# OK1050-C_V1_2_Connect.net
KiCad netlist of a schematic drawn in Altium Designer
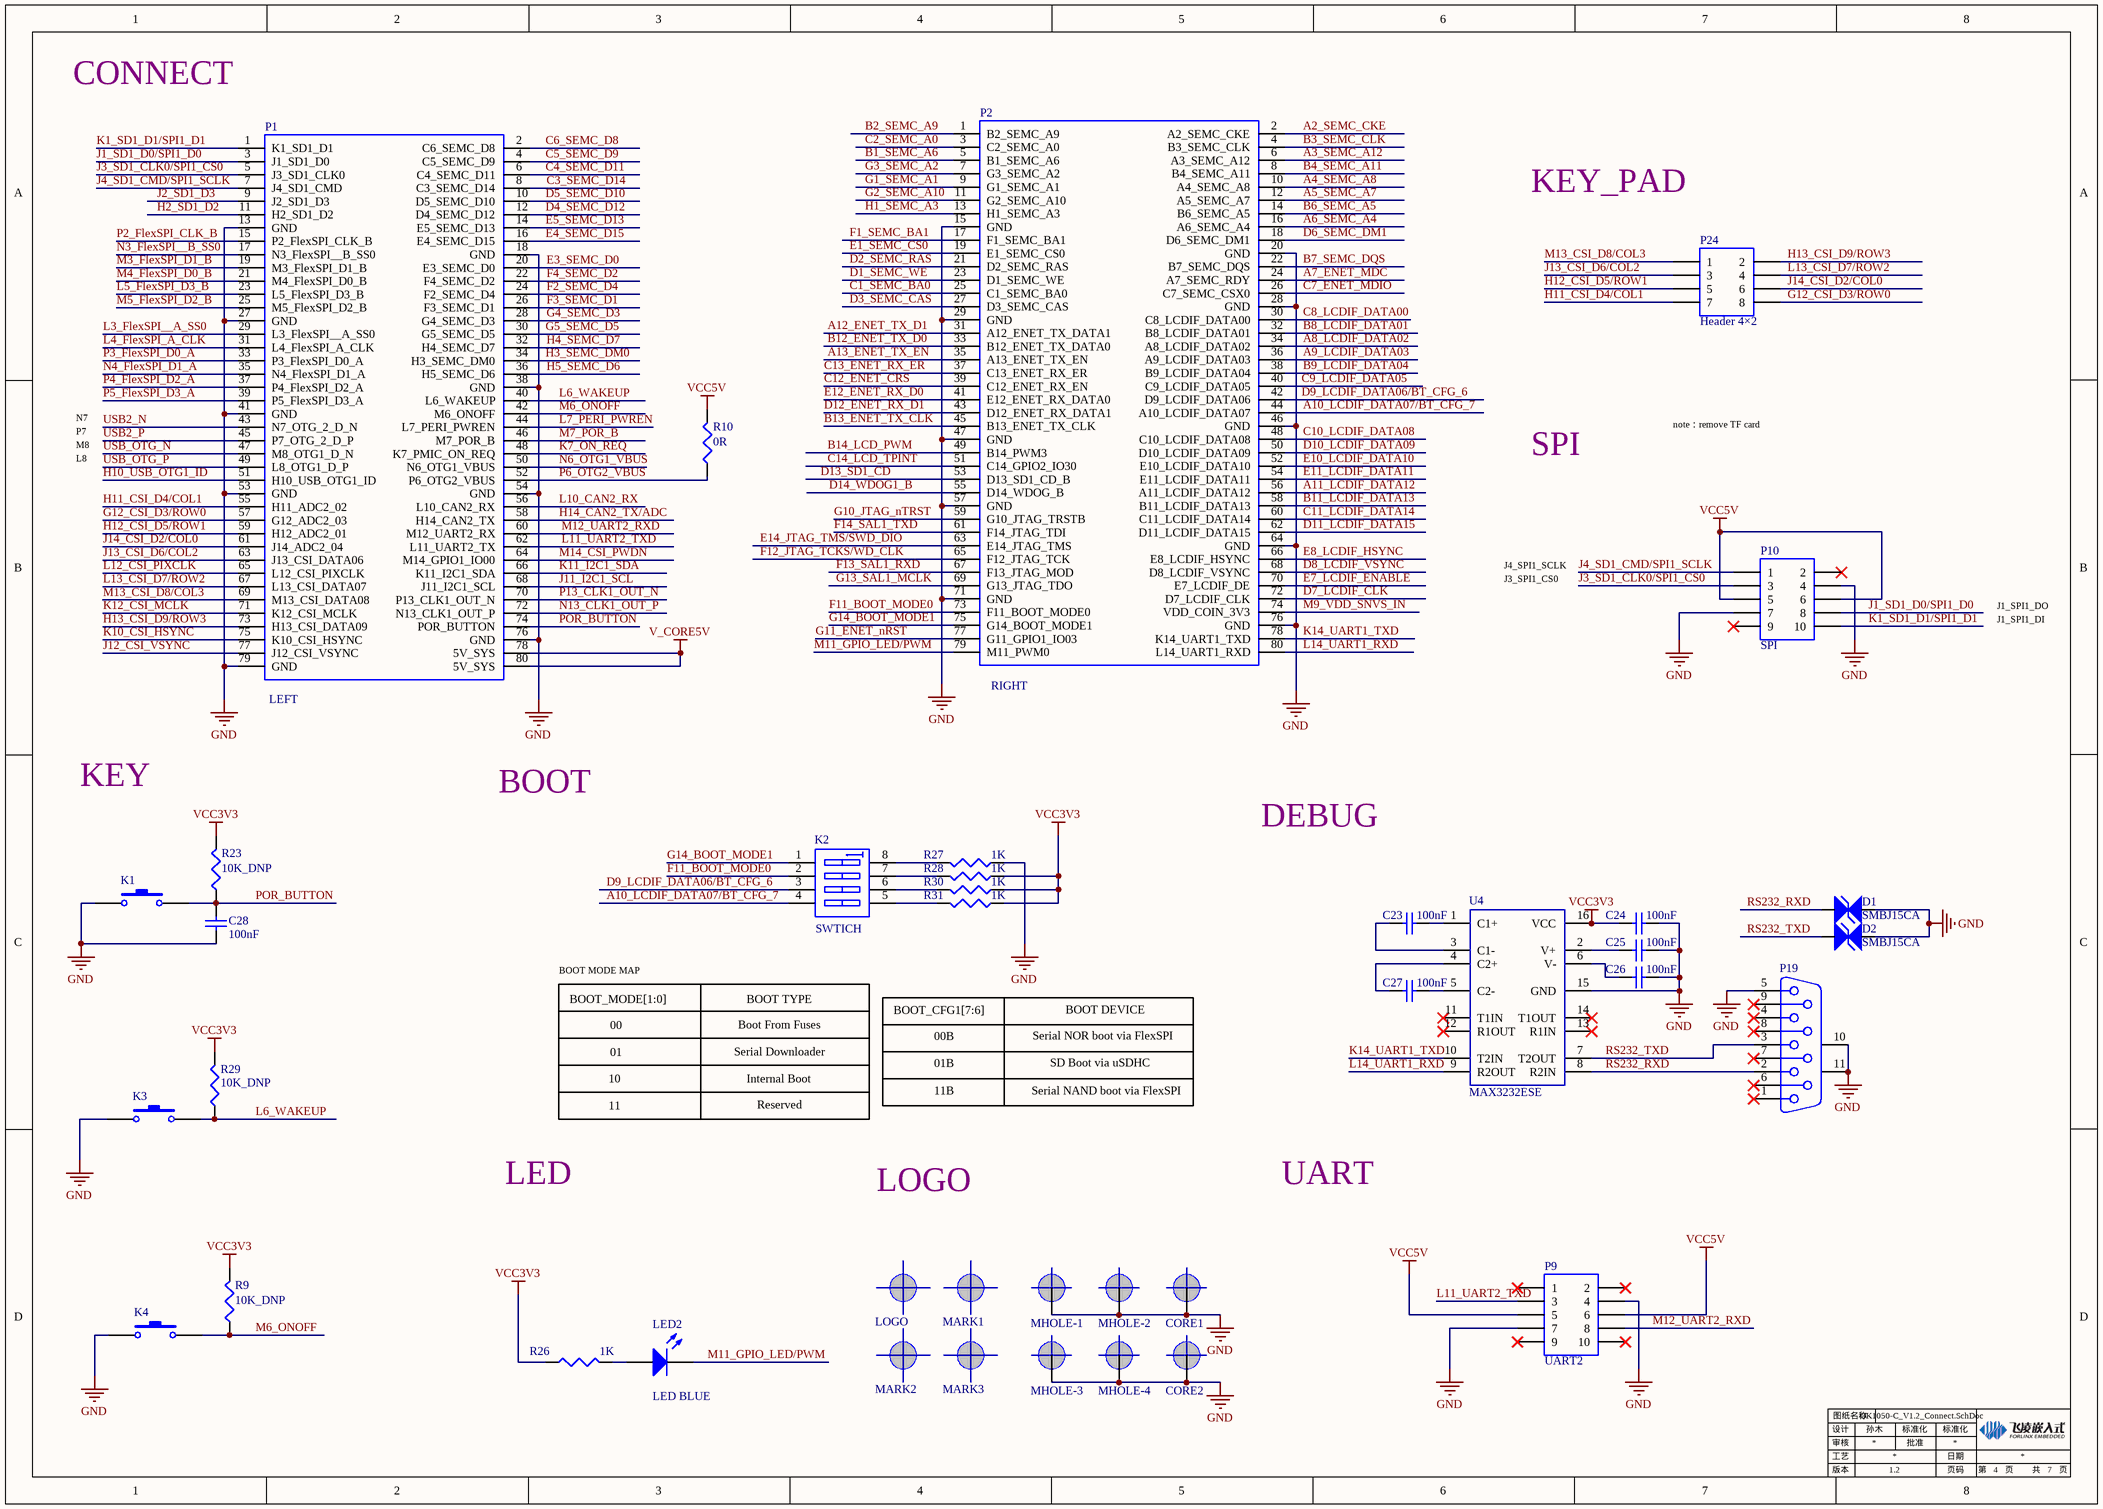
[diagram p0: OK1050-C_V1.2_Connect.SchDoc]

(export (version "E")
  (design (tool "Eeschema 10.0.6"))
  (components
    (comp (ref "C23")
      (value "100nF")
      (footprint "0603C+")
      (description "Capacitor")
      (fields (field (name "PUBLISHER") "Altium Limited"))
      (libsource (lib "Miscellaneous Devices") (part "Cap"))
    )
    (comp (ref "C24")
      (value "100nF")
      (footprint "0603C+")
      (description "Capacitor")
      (fields (field (name "PUBLISHER") "Altium Limited"))
      (libsource (lib "Miscellaneous Devices") (part "Cap"))
    )
    (comp (ref "C25")
      (value "100nF")
      (footprint "0603C+")
      (description "Capacitor")
      (fields (field (name "PUBLISHER") "Altium Limited"))
      (libsource (lib "Miscellaneous Devices") (part "Cap"))
    )
    (comp (ref "C26")
      (value "100nF")
      (footprint "0603C+")
      (description "Capacitor")
      (fields (field (name "PUBLISHER") "Altium Limited"))
      (libsource (lib "Miscellaneous Devices") (part "Cap"))
    )
    (comp (ref "C27")
      (value "100nF")
      (footprint "0603C+")
      (description "Capacitor")
      (fields (field (name "PUBLISHER") "Altium Limited"))
      (libsource (lib "Miscellaneous Devices") (part "Cap"))
    )
    (comp (ref "C28")
      (value "100nF")
      (footprint "0603C+")
      (description "Capacitor")
      (fields (field (name "PUBLISHER") "Altium Limited"))
      (libsource (lib "Miscellaneous Devices") (part "Cap"))
    )
    (comp (ref "D1") (value "SMBJ15CA") (footprint "SMB/DO-214AA") (libsource (lib "Sch") (part "TVS")))
    (comp (ref "D2") (value "SMBJ15CA") (footprint "SMB/DO-214AA") (libsource (lib "Sch") (part "TVS")))
    (comp (ref "K1")
      (value "6*6*5侧位带支架")
      (description "Switch")
      (fields (field (name "PUBLISHER") "Altium Limited"))
      (libsource (lib "Miscellaneous Devices") (part "SW-PB"))
    )
    (comp (ref "K2")
      (value "SWTICH")
      (footprint "SMD_4")
      (libsource (lib "PCB_RT1052_1") (part "SWTICH_DIP6"))
    )
    (comp (ref "K3")
      (value "6*6*5侧位2脚带支架")
      (description "Switch")
      (fields (field (name "PUBLISHER") "Altium Limited"))
      (libsource (lib "Miscellaneous Devices") (part "SW-PB"))
    )
    (comp (ref "K4")
      (value "6*6*5侧位2脚带支架")
      (description "Switch")
      (fields (field (name "PUBLISHER") "Altium Limited"))
      (libsource (lib "Miscellaneous Devices") (part "SW-PB"))
    )
    (comp (ref "LED2")
      (value "LED_BULE")
      (footprint "LED0603_M1608")
      (description "Typical RED, GREEN, YELLOW, AMBER GaAs LED")
      (fields (field (name "BOOK") "LED BLUE") (field (name "PUBLISHER") "Altium Limited"))
      (libsource (lib "NET-LCD-USB") (part "LED2"))
    )
    (comp (ref "LOGO1") (value "LOGO") (footprint "LOGO") (libsource (lib "IMX6QP-C") (part "MHOLE_1")))
    (comp (ref "M1")
      (value "MHOLE-1")
      (footprint "3.2mm_hole")
      (libsource (lib "IMX6QP-C") (part "MHOLE-2_1"))
    )
    (comp (ref "M2") (value "MHOLE-2") (footprint "3.2mm_hole") (libsource (lib "IMX6QP-C") (part "MHOLE-2")))
    (comp (ref "M3")
      (value "MHOLE-3")
      (footprint "3.2mm_hole")
      (libsource (lib "IMX6QP-C") (part "MHOLE-2_1"))
    )
    (comp (ref "M4")
      (value "MHOLE-4")
      (footprint "3.2mm_hole")
      (libsource (lib "IMX6QP-C") (part "MHOLE-2_1"))
    )
    (comp (ref "M5") (value "CORE1") (footprint "2.1mm_hole") (libsource (lib "IMX6QP-C") (part "MHOLE-2")))
    (comp (ref "M6") (value "CORE2") (footprint "2.1mm_hole") (libsource (lib "IMX6QP-C") (part "MHOLE-2_1")))
    (comp (ref "Mark1") (value "MARK1") (footprint "MARK POINT") (libsource (lib "IMX6QP-C") (part "MHOLE")))
    (comp (ref "Mark2") (value "MARK2") (footprint "MARK POINT") (libsource (lib "IMX6QP-C") (part "MHOLE")))
    (comp (ref "Mark3") (value "MARK3") (footprint "MARK POINT") (libsource (lib "IMX6QP-C") (part "MHOLE")))
    (comp (ref "P1")
      (value "LEFT")
      (footprint "CON80")
      (description "Header, 30-Pin, Dual row")
      (fields (field (name "PUBLISHER") "Altium Limited"))
      (libsource (lib "PCB_RT1052_1") (part "Header40X2_left"))
    )
    (comp (ref "P2")
      (value "RIGHT")
      (footprint "CON80")
      (description "Header, 30-Pin, Dual row")
      (fields (field (name "PUBLISHER") "Altium Limited"))
      (libsource (lib "PCB_RT1052_1") (part "Header40X2_right"))
    )
    (comp (ref "P9")
      (value "UART2")
      (description "Header, 5-Pin, Dual row")
      (fields (field (name "PUBLISHER") "Altium Limited"))
      (libsource (lib "PCB_RT1052") (part "Header 5X2"))
    )
    (comp (ref "P10")
      (value "SPI")
      (description "Header, 5-Pin, Dual row")
      (fields (field (name "PUBLISHER") "Altium Limited"))
      (libsource (lib "PCB_RT1052") (part "Header 5X2"))
    )
    (comp (ref "P19")
      (value "DEBUG")
      (footprint "DSUB1.385-2H9-M")
      (description "Receptacle Assembly, 9 Position, Right Angle")
      (fields (field (name "PUBLISHER") "Altium Limited"))
      (libsource (lib "Miscellaneous Connectors") (part "D Connector 9"))
    )
    (comp (ref "P24")
      (value "Header 4×2")
      (footprint "HDR2X4")
      (libsource (lib "PCB_RT1052") (part "Header 4×2"))
    )
    (comp (ref "R9")
      (value "10K_DNP")
      (footprint "0603R+")
      (description "Resistor")
      (fields (field (name "PUBLISHER") "Altium Limited"))
      (libsource (lib "Miscellaneous Devices") (part "Res3"))
    )
    (comp (ref "R10")
      (value "0R")
      (footprint "0603R+")
      (description "Resistor")
      (fields (field (name "PUBLISHER") "Altium Limited"))
      (libsource (lib "Miscellaneous Devices") (part "Res3"))
    )
    (comp (ref "R23")
      (value "10K_DNP")
      (footprint "0603R+")
      (description "Resistor")
      (fields (field (name "PUBLISHER") "Altium Limited"))
      (libsource (lib "Miscellaneous Devices") (part "Res3"))
    )
    (comp (ref "R26")
      (value "1K")
      (footprint "0603R+")
      (description "Resistor")
      (fields (field (name "PUBLISHER") "Altium Limited"))
      (libsource (lib "Miscellaneous Devices") (part "Res3"))
    )
    (comp (ref "R27")
      (value "1K")
      (footprint "0603R+")
      (description "Resistor")
      (fields (field (name "PUBLISHER") "Altium Limited"))
      (libsource (lib "Miscellaneous Devices") (part "Res3"))
    )
    (comp (ref "R28")
      (value "1K")
      (footprint "0603R+")
      (description "Resistor")
      (fields (field (name "PUBLISHER") "Altium Limited"))
      (libsource (lib "Miscellaneous Devices") (part "Res3"))
    )
    (comp (ref "R29")
      (value "10K_DNP")
      (footprint "0603R+")
      (description "Resistor")
      (fields (field (name "PUBLISHER") "Altium Limited"))
      (libsource (lib "Miscellaneous Devices") (part "Res3"))
    )
    (comp (ref "R30")
      (value "1K")
      (footprint "0603R+")
      (description "Resistor")
      (fields (field (name "PUBLISHER") "Altium Limited"))
      (libsource (lib "Miscellaneous Devices") (part "Res3"))
    )
    (comp (ref "R31")
      (value "1K")
      (footprint "0603R+")
      (description "Resistor")
      (fields (field (name "PUBLISHER") "Altium Limited"))
      (libsource (lib "Miscellaneous Devices") (part "Res3"))
    )
    (comp (ref "U4") (value "MAX3232ESE") (footprint "SOIC-16N") (libsource (lib "Sch") (part "MAX3232")))
  )
  (nets
    (net (code "1") (name "/A2_SEMC_CKE") (class "Default")
      (node (ref "P2") (pin "2") (pinfunction "A2_SEMC_CKE_2") (pintype "passive"))
    )
    (net (code "2") (name "/A3_SEMC_A12") (class "Default")
      (node (ref "P2") (pin "6") (pinfunction "A3_SEMC_A12_6") (pintype "passive"))
    )
    (net (code "3") (name "/A4_SEMC_A8") (class "Default")
      (node (ref "P2") (pin "10") (pinfunction "A4_SEMC_A8_10") (pintype "passive"))
    )
    (net (code "4") (name "/A5_SEMC_A7") (class "Default")
      (node (ref "P2") (pin "12") (pinfunction "A5_SEMC_A7_12") (pintype "passive"))
    )
    (net (code "5") (name "/A6_SEMC_A4") (class "Default")
      (node (ref "P2") (pin "16") (pinfunction "A6_SEMC_A4_16") (pintype "passive"))
    )
    (net (code "6") (name "/A7_ENET_MDC") (class "Default")
      (node (ref "P2") (pin "24") (pinfunction "A7_SEMC_RDY_24") (pintype "passive"))
    )
    (net (code "7") (name "/A8_LCDIF_DATA02") (class "Default")
      (node (ref "P2") (pin "34") (pinfunction "A8_LCDIF_DATA02_34") (pintype "passive"))
    )
    (net (code "8") (name "/A9_LCDIF_DATA03") (class "Default")
      (node (ref "P2") (pin "36") (pinfunction "A9_LCDIF_DATA03_36") (pintype "passive"))
    )
    (net (code "9") (name "/A10_LCDIF_DATA07{slash}BT_CFG_7") (class "Default")
      (node (ref "K2") (pin "4") (pinfunction "A4_4") (pintype "passive"))
      (node (ref "P2") (pin "44") (pinfunction "A10_LCDIF_DATA07_44") (pintype "passive"))
    )
    (net (code "10") (name "/A11_LCDIF_DATA12") (class "Default")
      (node (ref "P2") (pin "56") (pinfunction "A11_LCDIF_DATA12_56") (pintype "passive"))
    )
    (net (code "11") (name "/A12_ENET_TX_D1") (class "Default")
      (node (ref "P2") (pin "31") (pinfunction "A12_ENET_TX_DATA1_31") (pintype "passive"))
    )
    (net (code "12") (name "/A13_ENET_TX_EN") (class "Default")
      (node (ref "P2") (pin "35") (pinfunction "A13_ENET_TX_EN_35") (pintype "passive"))
    )
    (net (code "13") (name "/B1_SEMC_A6") (class "Default")
      (node (ref "P2") (pin "5") (pinfunction "B1_SEMC_A6_5") (pintype "passive"))
    )
    (net (code "14") (name "/B2_SEMC_A9") (class "Default")
      (node (ref "P2") (pin "1") (pinfunction "B2_SEMC_A9_1") (pintype "passive"))
    )
    (net (code "15") (name "/B3_SEMC_CLK") (class "Default")
      (node (ref "P2") (pin "4") (pinfunction "B3_SEMC_CLK_4") (pintype "passive"))
    )
    (net (code "16") (name "/B4_SEMC_A11") (class "Default")
      (node (ref "P2") (pin "8") (pinfunction "B4_SEMC_A11_8") (pintype "passive"))
    )
    (net (code "17") (name "/B6_SEMC_A5") (class "Default")
      (node (ref "P2") (pin "14") (pinfunction "B6_SEMC_A5_14") (pintype "passive"))
    )
    (net (code "18") (name "/B7_SEMC_DQS") (class "Default")
      (node (ref "P2") (pin "22") (pinfunction "B7_SEMC_DQS_22") (pintype "passive"))
    )
    (net (code "19") (name "/B8_LCDIF_DATA01") (class "Default")
      (node (ref "P2") (pin "32") (pinfunction "B8_LCDIF_DATA01_32") (pintype "passive"))
    )
    (net (code "20") (name "/B9_LCDIF_DATA04") (class "Default")
      (node (ref "P2") (pin "38") (pinfunction "B9_LCDIF_DATA04_38") (pintype "passive"))
    )
    (net (code "21") (name "/B11_LCDIF_DATA13") (class "Default")
      (node (ref "P2") (pin "58") (pinfunction "B11_LCDIF_DATA13_58") (pintype "passive"))
    )
    (net (code "22") (name "/B12_ENET_TX_D0") (class "Default")
      (node (ref "P2") (pin "33") (pinfunction "B12_ENET_TX_DATA0_33") (pintype "passive"))
    )
    (net (code "23") (name "/B13_ENET_TX_CLK") (class "Default")
      (node (ref "P2") (pin "45") (pinfunction "B13_ENET_TX_CLK_45") (pintype "passive"))
    )
    (net (code "24") (name "/B14_LCD_PWM") (class "Default")
      (node (ref "P2") (pin "49") (pinfunction "B14_PWM3_49") (pintype "passive"))
    )
    (net (code "25") (name "/C1_SEMC_BA0") (class "Default")
      (node (ref "P2") (pin "25") (pinfunction "C1_SEMC_BA0_25") (pintype "passive"))
    )
    (net (code "26") (name "/C2_SEMC_A0") (class "Default")
      (node (ref "P2") (pin "3") (pinfunction "C2_SEMC_A0_3") (pintype "passive"))
    )
    (net (code "27") (name "/C3_SEMC_D14") (class "Default")
      (node (ref "P1") (pin "8") (pinfunction "C3_SEMC_D14_8") (pintype "passive"))
    )
    (net (code "28") (name "/C4_SEMC_D11") (class "Default")
      (node (ref "P1") (pin "6") (pinfunction "C4_SEMC_D11_6") (pintype "passive"))
    )
    (net (code "29") (name "/C5_SEMC_D9") (class "Default")
      (node (ref "P1") (pin "4") (pinfunction "C5_SEMC_D9_4") (pintype "passive"))
    )
    (net (code "30") (name "/C6_SEMC_D8") (class "Default")
      (node (ref "P1") (pin "2") (pinfunction "C6_SEMC_D8_2") (pintype "passive"))
    )
    (net (code "31") (name "/C7_ENET_MDIO") (class "Default")
      (node (ref "P2") (pin "26") (pinfunction "C7_SEMC_CSX0_26") (pintype "passive"))
    )
    (net (code "32") (name "/C8_LCDIF_DATA00") (class "Default")
      (node (ref "P2") (pin "30") (pinfunction "C8_LCDIF_DATA00_30") (pintype "passive"))
    )
    (net (code "33") (name "/C9_LCDIF_DATA05") (class "Default")
      (node (ref "P2") (pin "40") (pinfunction "C9_LCDIF_DATA05_40") (pintype "passive"))
    )
    (net (code "34") (name "/C10_LCDIF_DATA08") (class "Default")
      (node (ref "P2") (pin "48") (pinfunction "C10_LCDIF_DATA08_48") (pintype "passive"))
    )
    (net (code "35") (name "/C11_LCDIF_DATA14") (class "Default")
      (node (ref "P2") (pin "60") (pinfunction "C11_LCDIF_DATA14_60") (pintype "passive"))
    )
    (net (code "36") (name "/C12_ENET_CRS") (class "Default")
      (node (ref "P2") (pin "39") (pinfunction "C12_ENET_RX_EN_39") (pintype "passive"))
    )
    (net (code "37") (name "/C13_ENET_RX_ER") (class "Default")
      (node (ref "P2") (pin "37") (pinfunction "C13_ENET_RX_ER_37") (pintype "passive"))
    )
    (net (code "38") (name "/C14_LCD_TPINT") (class "Default")
      (node (ref "P2") (pin "51") (pinfunction "C14_GPIO2_IO30_51") (pintype "passive"))
    )
    (net (code "39") (name "/D1_SEMC_WE") (class "Default")
      (node (ref "P2") (pin "23") (pinfunction "D1_SEMC_WE_23") (pintype "passive"))
    )
    (net (code "40") (name "/D2_SEMC_RAS") (class "Default")
      (node (ref "P2") (pin "21") (pinfunction "D2_SEMC_RAS_21") (pintype "passive"))
    )
    (net (code "41") (name "/D3_SEMC_CAS") (class "Default")
      (node (ref "P2") (pin "27") (pinfunction "D3_SEMC_CAS_27") (pintype "passive"))
    )
    (net (code "42") (name "/D4_SEMC_D12") (class "Default")
      (node (ref "P1") (pin "12") (pinfunction "D4_SEMC_D12_12") (pintype "passive"))
    )
    (net (code "43") (name "/D5_SEMC_D10") (class "Default")
      (node (ref "P1") (pin "10") (pinfunction "D5_SEMC_D10_10") (pintype "passive"))
    )
    (net (code "44") (name "/D6_SEMC_DM1") (class "Default")
      (node (ref "P2") (pin "18") (pinfunction "D6_SEMC_DM1_18") (pintype "passive"))
    )
    (net (code "45") (name "/D7_LCDIF_CLK") (class "Default")
      (node (ref "P2") (pin "72") (pinfunction "D7_LCDIF_CLK_72") (pintype "passive"))
    )
    (net (code "46") (name "/D8_LCDIF_VSYNC") (class "Default")
      (node (ref "P2") (pin "68") (pinfunction "D8_LCDIF_VSYNC_68") (pintype "passive"))
    )
    (net (code "47") (name "/D9_LCDIF_DATA06{slash}BT_CFG_6") (class "Default")
      (node (ref "K2") (pin "3") (pinfunction "A3_3") (pintype "passive"))
      (node (ref "P2") (pin "42") (pinfunction "D9_LCDIF_DATA06_42") (pintype "passive"))
    )
    (net (code "48") (name "/D10_LCDIF_DATA09") (class "Default")
      (node (ref "P2") (pin "50") (pinfunction "D10_LCDIF_DATA09_50") (pintype "passive"))
    )
    (net (code "49") (name "/D11_LCDIF_DATA15") (class "Default")
      (node (ref "P2") (pin "62") (pinfunction "D11_LCDIF_DATA15_62") (pintype "passive"))
    )
    (net (code "50") (name "/D12_ENET_RX_D1") (class "Default")
      (node (ref "P2") (pin "43") (pinfunction "D12_ENET_RX_DATA1_43") (pintype "passive"))
    )
    (net (code "51") (name "/D13_SD1_CD") (class "Default")
      (node (ref "P2") (pin "53") (pinfunction "D13_SD1_CD_B_53") (pintype "passive"))
    )
    (net (code "52") (name "/D14_WDOG1_B") (class "Default")
      (node (ref "P2") (pin "55") (pinfunction "D14_WDOG_B_55") (pintype "passive"))
    )
    (net (code "53") (name "/E1_SEMC_CS0") (class "Default")
      (node (ref "P2") (pin "19") (pinfunction "E1_SEMC_CS0_19") (pintype "passive"))
    )
    (net (code "54") (name "/E3_SEMC_D0") (class "Default")
      (node (ref "P1") (pin "20") (pinfunction "E3_SEMC_D0_20") (pintype "passive"))
    )
    (net (code "55") (name "/E4_SEMC_D15") (class "Default")
      (node (ref "P1") (pin "16") (pinfunction "E4_SEMC_D15_16") (pintype "passive"))
    )
    (net (code "56") (name "/E5_SEMC_D13") (class "Default")
      (node (ref "P1") (pin "14") (pinfunction "E5_SEMC_D13_14") (pintype "passive"))
    )
    (net (code "57") (name "/E7_LCDIF_ENABLE") (class "Default")
      (node (ref "P2") (pin "70") (pinfunction "E7_LCDIF_DE_70") (pintype "passive"))
    )
    (net (code "58") (name "/E8_LCDIF_HSYNC") (class "Default")
      (node (ref "P2") (pin "66") (pinfunction "E8_LCDIF_HSYNC_66") (pintype "passive"))
    )
    (net (code "59") (name "/E10_LCDIF_DATA10") (class "Default")
      (node (ref "P2") (pin "52") (pinfunction "E10_LCDIF_DATA10_52") (pintype "passive"))
    )
    (net (code "60") (name "/E11_LCDIF_DATA11") (class "Default")
      (node (ref "P2") (pin "54") (pinfunction "E11_LCDIF_DATA11_54") (pintype "passive"))
    )
    (net (code "61") (name "/E12_ENET_RX_D0") (class "Default")
      (node (ref "P2") (pin "41") (pinfunction "E12_ENET_RX_DATA0_41") (pintype "passive"))
    )
    (net (code "62") (name "/E14_JTAG_TMS{slash}SWD_DIO") (class "Default")
      (node (ref "P2") (pin "63") (pinfunction "E14_JTAG_TMS_63") (pintype "passive"))
    )
    (net (code "63") (name "/F1_SEMC_BA1") (class "Default")
      (node (ref "P2") (pin "17") (pinfunction "F1_SEMC_BA1_17") (pintype "passive"))
    )
    (net (code "64") (name "/F2_SEMC_D4") (class "Default")
      (node (ref "P1") (pin "24") (pinfunction "F2_SEMC_D4_24") (pintype "passive"))
    )
    (net (code "65") (name "/F3_SEMC_D1") (class "Default")
      (node (ref "P1") (pin "26") (pinfunction "F3_SEMC_D1_26") (pintype "passive"))
    )
    (net (code "66") (name "/F4_SEMC_D2") (class "Default")
      (node (ref "P1") (pin "22") (pinfunction "F4_SEMC_D2_22") (pintype "passive"))
    )
    (net (code "67") (name "/F11_BOOT_MODE0") (class "Default")
      (node (ref "K2") (pin "2") (pinfunction "A2_2") (pintype "passive"))
      (node (ref "P2") (pin "73") (pinfunction "F11_BOOT_MODE0_73") (pintype "passive"))
    )
    (net (code "68") (name "/F12_JTAG_TCKS{slash}WD_CLK") (class "Default")
      (node (ref "P2") (pin "65") (pinfunction "F12_JTAG_TCK_65") (pintype "passive"))
    )
    (net (code "69") (name "/F13_SAL1_RXD") (class "Default")
      (node (ref "P2") (pin "67") (pinfunction "F13_JTAG_MOD_67") (pintype "passive"))
    )
    (net (code "70") (name "/F14_SAL1_TXD") (class "Default")
      (node (ref "P2") (pin "61") (pinfunction "F14_JTAG_TDI_61") (pintype "passive"))
    )
    (net (code "71") (name "/G1_SEMC_A1") (class "Default")
      (node (ref "P2") (pin "9") (pinfunction "G1_SEMC_A1_9") (pintype "passive"))
    )
    (net (code "72") (name "/G2_SEMC_A10") (class "Default")
      (node (ref "P2") (pin "11") (pinfunction "G2_SEMC_A10_11") (pintype "passive"))
    )
    (net (code "73") (name "/G3_SEMC_A2") (class "Default")
      (node (ref "P2") (pin "7") (pinfunction "G3_SEMC_A2_7") (pintype "passive"))
    )
    (net (code "74") (name "/G4_SEMC_D3") (class "Default")
      (node (ref "P1") (pin "28") (pinfunction "G4_SEMC_D3_28") (pintype "passive"))
    )
    (net (code "75") (name "/G5_SEMC_D5") (class "Default")
      (node (ref "P1") (pin "30") (pinfunction "G5_SEMC_D5_30") (pintype "passive"))
    )
    (net (code "76") (name "/G10_JTAG_nTRST") (class "Default")
      (node (ref "P2") (pin "59") (pinfunction "G10_JTAG_TRSTB_59") (pintype "passive"))
    )
    (net (code "77") (name "/G11_ENET_nRST") (class "Default")
      (node (ref "P2") (pin "77") (pinfunction "G11_GPIO1_IO03_77") (pintype "passive"))
    )
    (net (code "78") (name "/G12_CSI_D3{slash}ROW0") (class "Default")
      (node (ref "P1") (pin "57") (pinfunction "G12_ADC2_03_57") (pintype "passive"))
      (node (ref "P24") (pin "8") (pinfunction "8_8") (pintype "passive"))
    )
    (net (code "79") (name "/G13_SAL1_MCLK") (class "Default")
      (node (ref "P2") (pin "69") (pinfunction "G13_JTAG_TDO_69") (pintype "passive"))
    )
    (net (code "80") (name "/G14_BOOT_MODE1") (class "Default")
      (node (ref "K2") (pin "1") (pinfunction "A1_1") (pintype "passive"))
      (node (ref "P2") (pin "75") (pinfunction "G14_BOOT_MODE1_75") (pintype "passive"))
    )
    (net (code "81") (name "/H1_SEMC_A3") (class "Default")
      (node (ref "P2") (pin "13") (pinfunction "H1_SEMC_A3_13") (pintype "passive"))
    )
    (net (code "82") (name "/H2_SD1_D2") (class "Default")
      (node (ref "P1") (pin "11") (pinfunction "H2_SD1_D2_11") (pintype "passive"))
    )
    (net (code "83") (name "/H3_SEMC_DM0") (class "Default")
      (node (ref "P1") (pin "34") (pinfunction "H3_SEMC_DM0_34") (pintype "passive"))
    )
    (net (code "84") (name "/H4_SEMC_D7") (class "Default")
      (node (ref "P1") (pin "32") (pinfunction "H4_SEMC_D7_32") (pintype "passive"))
    )
    (net (code "85") (name "/H5_SEMC_D6") (class "Default")
      (node (ref "P1") (pin "36") (pinfunction "H5_SEMC_D6_36") (pintype "passive"))
    )
    (net (code "86") (name "/H10_USB_OTG1_ID") (class "Default")
      (node (ref "P1") (pin "51") (pinfunction "H10_USB_OTG1_ID_51") (pintype "passive"))
    )
    (net (code "87") (name "/H11_CSI_D4{slash}COL1") (class "Default")
      (node (ref "P1") (pin "55") (pinfunction "H11_ADC2_02_55") (pintype "passive"))
      (node (ref "P24") (pin "7") (pinfunction "7_7") (pintype "passive"))
    )
    (net (code "88") (name "/H12_CSI_D5{slash}ROW1") (class "Default")
      (node (ref "P1") (pin "59") (pinfunction "H12_ADC2_01_59") (pintype "passive"))
      (node (ref "P24") (pin "5") (pinfunction "5_5") (pintype "passive"))
    )
    (net (code "89") (name "/H13_CSI_D9{slash}ROW3") (class "Default")
      (node (ref "P1") (pin "73") (pinfunction "H13_CSI_DATA09_73") (pintype "passive"))
      (node (ref "P24") (pin "2") (pinfunction "2_2") (pintype "passive"))
    )
    (net (code "90") (name "/H14_CAN2_TX{slash}ADC") (class "Default")
      (node (ref "P1") (pin "58") (pinfunction "H14_CAN2_TX_58") (pintype "passive"))
    )
    (net (code "91") (name "/J1_SD1_D0{slash}SPI1_D0") (class "Default")
      (node (ref "P1") (pin "3") (pinfunction "J1_SD1_D0_3") (pintype "passive"))
      (node (ref "P10") (pin "8") (pinfunction "8_8") (pintype "passive"))
    )
    (net (code "92") (name "/J2_SD1_D3") (class "Default")
      (node (ref "P1") (pin "9") (pinfunction "J2_SD1_D3_9") (pintype "passive"))
    )
    (net (code "93") (name "/J3_SD1_CLK0{slash}SPI1_CS0") (class "Default")
      (node (ref "P1") (pin "5") (pinfunction "J3_SD1_CLK0_5") (pintype "passive"))
      (node (ref "P10") (pin "3") (pinfunction "3_3") (pintype "passive"))
    )
    (net (code "94") (name "/J4_SD1_CMD{slash}SPI1_SCLK") (class "Default")
      (node (ref "P1") (pin "7") (pinfunction "J4_SD1_CMD_7") (pintype "passive"))
      (node (ref "P10") (pin "1") (pinfunction "1_1") (pintype "passive"))
    )
    (net (code "95") (name "/J11_I2C1_SCL") (class "Default")
      (node (ref "P1") (pin "68") (pinfunction "J11_I2C1_SCL_68") (pintype "passive"))
    )
    (net (code "96") (name "/J12_CSI_VSYNC") (class "Default")
      (node (ref "P1") (pin "77") (pinfunction "J12_CSI_VSYNC_77") (pintype "passive"))
    )
    (net (code "97") (name "/J13_CSI_D6{slash}COL2") (class "Default")
      (node (ref "P1") (pin "63") (pinfunction "J13_CSI_DATA06_63") (pintype "passive"))
      (node (ref "P24") (pin "3") (pinfunction "3_3") (pintype "passive"))
    )
    (net (code "98") (name "/J14_CSI_D2{slash}COL0") (class "Default")
      (node (ref "P1") (pin "61") (pinfunction "J14_ADC2_04_61") (pintype "passive"))
      (node (ref "P24") (pin "6") (pinfunction "6_6") (pintype "passive"))
    )
    (net (code "99") (name "/K1_SD1_D1{slash}SPI1_D1") (class "Default")
      (node (ref "P1") (pin "1") (pinfunction "K1_SD1_D1_1") (pintype "passive"))
      (node (ref "P10") (pin "10") (pinfunction "10_10") (pintype "passive"))
    )
    (net (code "100") (name "/K7_ON_REQ") (class "Default")
      (node (ref "P1") (pin "48") (pinfunction "K7_PMIC_ON_REQ_48") (pintype "passive"))
    )
    (net (code "101") (name "/K10_CSI_HSYNC") (class "Default")
      (node (ref "P1") (pin "75") (pinfunction "K10_CSI_HSYNC_75") (pintype "passive"))
    )
    (net (code "102") (name "/K11_I2C1_SDA") (class "Default")
      (node (ref "P1") (pin "66") (pinfunction "K11_I2C1_SDA_66") (pintype "passive"))
    )
    (net (code "103") (name "/K12_CSI_MCLK") (class "Default")
      (node (ref "P1") (pin "71") (pinfunction "K12_CSI_MCLK_71") (pintype "passive"))
    )
    (net (code "104") (name "/K14_UART1_TXD") (class "Default")
      (node (ref "P2") (pin "78") (pinfunction "K14_UART1_TXD_78") (pintype "passive"))
      (node (ref "U4") (pin "10") (pinfunction "T2IN_10") (pintype "passive"))
    )
    (net (code "105") (name "/L3_FlexSPI__A_SS0") (class "Default")
      (node (ref "P1") (pin "29") (pinfunction "L3_FlexSPI__A_SS0_29") (pintype "passive"))
    )
    (net (code "106") (name "/L4_FlexSPI_A_CLK") (class "Default")
      (node (ref "P1") (pin "31") (pinfunction "L4_FlexSPI_A_CLK_31") (pintype "passive"))
    )
    (net (code "107") (name "/L5_FlexSPI_D3_B") (class "Default")
      (node (ref "P1") (pin "23") (pinfunction "L5_FlexSPI_D3_B_23") (pintype "passive"))
    )
    (net (code "108") (name "/L6_WAKEUP") (class "Default")
      (node (ref "K3") (pin "2") (pinfunction "2_2") (pintype "passive"))
      (node (ref "P1") (pin "40") (pinfunction "L6_WAKEUP_40") (pintype "passive"))
      (node (ref "R29") (pin "1") (pinfunction "1_1") (pintype "passive"))
    )
    (net (code "109") (name "/L7_PERI_PWREN") (class "Default")
      (node (ref "P1") (pin "44") (pinfunction "L7_PERI_PWREN_44") (pintype "passive"))
    )
    (net (code "110") (name "/L10_CAN2_RX") (class "Default")
      (node (ref "P1") (pin "56") (pinfunction "L10_CAN2_RX_56") (pintype "passive"))
    )
    (net (code "111") (name "/L11_UART2_TXD") (class "Default")
      (node (ref "P1") (pin "62") (pinfunction "L11_UART2_TX_62") (pintype "passive"))
      (node (ref "P9") (pin "3") (pinfunction "3_3") (pintype "passive"))
    )
    (net (code "112") (name "/L12_CSI_PIXCLK") (class "Default")
      (node (ref "P1") (pin "65") (pinfunction "L12_CSI_PIXCLK_65") (pintype "passive"))
    )
    (net (code "113") (name "/L13_CSI_D7{slash}ROW2") (class "Default")
      (node (ref "P1") (pin "67") (pinfunction "L13_CSI_DATA07_67") (pintype "passive"))
      (node (ref "P24") (pin "4") (pinfunction "4_4") (pintype "passive"))
    )
    (net (code "114") (name "/L14_UART1_RXD") (class "Default")
      (node (ref "P2") (pin "80") (pinfunction "L14_UART1_RXD_80") (pintype "passive"))
      (node (ref "U4") (pin "9") (pinfunction "R2OUT_9") (pintype "passive"))
    )
    (net (code "115") (name "/M3_FlexSPI_D1_B") (class "Default")
      (node (ref "P1") (pin "19") (pinfunction "M3_FlexSPI_D1_B_19") (pintype "passive"))
    )
    (net (code "116") (name "/M4_FlexSPI_D0_B") (class "Default")
      (node (ref "P1") (pin "21") (pinfunction "M4_FlexSPI_D0_B_21") (pintype "passive"))
    )
    (net (code "117") (name "/M5_FlexSPI_D2_B") (class "Default")
      (node (ref "P1") (pin "25") (pinfunction "M5_FlexSPI_D2_B_25") (pintype "passive"))
    )
    (net (code "118") (name "/M6_ONOFF") (class "Default")
      (node (ref "K4") (pin "2") (pinfunction "2_2") (pintype "passive"))
      (node (ref "P1") (pin "42") (pinfunction "M6_ONOFF_42") (pintype "passive"))
      (node (ref "R9") (pin "1") (pinfunction "1_1") (pintype "passive"))
    )
    (net (code "119") (name "/M7_POR_B") (class "Default")
      (node (ref "P1") (pin "46") (pinfunction "M7_POR_B_46") (pintype "passive"))
    )
    (net (code "120") (name "/M9_VDD_SNVS_IN") (class "Default")
      (node (ref "P2") (pin "74") (pinfunction "VDD_COIN_3V3_74") (pintype "passive"))
    )
    (net (code "121") (name "/M11_GPIO_LED{slash}PWM") (class "Default")
      (node (ref "LED2") (pin "2") (pinfunction "K_2") (pintype "passive"))
      (node (ref "P2") (pin "79") (pinfunction "M11_PWM0_79") (pintype "passive"))
    )
    (net (code "122") (name "/M12_UART2_RXD") (class "Default")
      (node (ref "P1") (pin "60") (pinfunction "M12_UART2_RX_60") (pintype "passive"))
      (node (ref "P9") (pin "8") (pinfunction "8_8") (pintype "passive"))
    )
    (net (code "123") (name "/M13_CSI_D8{slash}COL3") (class "Default")
      (node (ref "P1") (pin "69") (pinfunction "M13_CSI_DATA08_69") (pintype "passive"))
      (node (ref "P24") (pin "1") (pinfunction "1_1") (pintype "passive"))
    )
    (net (code "124") (name "/M14_CSI_PWDN") (class "Default")
      (node (ref "P1") (pin "64") (pinfunction "M14_GPIO1_IO00_64") (pintype "passive"))
    )
    (net (code "125") (name "/N3_FlexSPI__B_SS0") (class "Default")
      (node (ref "P1") (pin "17") (pinfunction "N3_FlexSPI__B_SS0_17") (pintype "passive"))
    )
    (net (code "126") (name "/N4_FlexSPI_D1_A") (class "Default")
      (node (ref "P1") (pin "35") (pinfunction "N4_FlexSPI_D1_A_35") (pintype "passive"))
    )
    (net (code "127") (name "/N6_OTG1_VBUS") (class "Default")
      (node (ref "P1") (pin "50") (pinfunction "N6_OTG1_VBUS_50") (pintype "passive"))
    )
    (net (code "128") (name "/N13_CLK1_OUT_P") (class "Default")
      (node (ref "P1") (pin "72") (pinfunction "N13_CLK1_OUT_P_72") (pintype "passive"))
    )
    (net (code "129") (name "/P2_FlexSPI_CLK_B") (class "Default")
      (node (ref "P1") (pin "15") (pinfunction "P2_FlexSPI_CLK_B_15") (pintype "passive"))
    )
    (net (code "130") (name "/P3_FlexSPI_D0_A") (class "Default")
      (node (ref "P1") (pin "33") (pinfunction "P3_FlexSPI_D0_A_33") (pintype "passive"))
    )
    (net (code "131") (name "/P4_FlexSPI_D2_A") (class "Default")
      (node (ref "P1") (pin "37") (pinfunction "P4_FlexSPI_D2_A_37") (pintype "passive"))
    )
    (net (code "132") (name "/P5_FlexSPI_D3_A") (class "Default")
      (node (ref "P1") (pin "39") (pinfunction "P5_FlexSPI_D3_A_39") (pintype "passive"))
    )
    (net (code "133") (name "/P6_OTG2_VBUS") (class "Default")
      (node (ref "P1") (pin "52") (pinfunction "P6_OTG2_VBUS_52") (pintype "passive"))
      (node (ref "R10") (pin "1") (pinfunction "1_1") (pintype "passive"))
    )
    (net (code "134") (name "/P13_CLK1_OUT_N") (class "Default")
      (node (ref "P1") (pin "70") (pinfunction "P13_CLK1_OUT_N_70") (pintype "passive"))
    )
    (net (code "135") (name "/POR_BUTTON") (class "Default")
      (node (ref "C28") (pin "2") (pinfunction "2_2") (pintype "passive"))
      (node (ref "K1") (pin "2") (pinfunction "2_2") (pintype "passive"))
      (node (ref "P1") (pin "74") (pinfunction "POR_BUTTON_74") (pintype "passive"))
      (node (ref "R23") (pin "1") (pinfunction "1_1") (pintype "passive"))
    )
    (net (code "136") (name "/RS232_RXD") (class "Default")
      (node (ref "D1") (pin "1") (pinfunction "1_1") (pintype "passive"))
      (node (ref "P19") (pin "2") (pinfunction "2_2") (pintype "passive"))
      (node (ref "U4") (pin "8") (pinfunction "R2IN_8") (pintype "passive"))
    )
    (net (code "137") (name "/RS232_TXD") (class "Default")
      (node (ref "D2") (pin "1") (pinfunction "1_1") (pintype "passive"))
      (node (ref "P19") (pin "3") (pinfunction "3_3") (pintype "passive"))
      (node (ref "U4") (pin "7") (pinfunction "T2OUT_7") (pintype "passive"))
    )
    (net (code "138") (name "/USB2_N") (class "Default")
      (node (ref "P1") (pin "43") (pinfunction "N7_OTG_2_D_N_43") (pintype "passive"))
    )
    (net (code "139") (name "/USB2_P") (class "Default")
      (node (ref "P1") (pin "45") (pinfunction "P7_OTG_2_D_P_45") (pintype "passive"))
    )
    (net (code "140") (name "/USB_OTG_N") (class "Default")
      (node (ref "P1") (pin "47") (pinfunction "M8_OTG1_D_N_47") (pintype "passive"))
    )
    (net (code "141") (name "/USB_OTG_P") (class "Default")
      (node (ref "P1") (pin "49") (pinfunction "L8_OTG1_D_P_49") (pintype "passive"))
    )
    (net (code "142") (name "GND") (class "Default")
      (node (ref "C24") (pin "1") (pinfunction "1_1") (pintype "passive"))
      (node (ref "C25") (pin "1") (pinfunction "1_1") (pintype "passive"))
      (node (ref "C26") (pin "1") (pinfunction "1_1") (pintype "passive"))
      (node (ref "C28") (pin "1") (pinfunction "1_1") (pintype "passive"))
      (node (ref "D1") (pin "2") (pinfunction "2_2") (pintype "passive"))
      (node (ref "D2") (pin "2") (pinfunction "2_2") (pintype "passive"))
      (node (ref "K1") (pin "1") (pinfunction "1_1") (pintype "passive"))
      (node (ref "K3") (pin "1") (pinfunction "1_1") (pintype "passive"))
      (node (ref "K4") (pin "1") (pinfunction "1_1") (pintype "passive"))
      (node (ref "M1") (pin "1") (pinfunction "EF_1") (pintype "passive"))
      (node (ref "M2") (pin "1") (pinfunction "EF_1") (pintype "passive"))
      (node (ref "M3") (pin "1") (pinfunction "EF_1") (pintype "passive"))
      (node (ref "M4") (pin "1") (pinfunction "EF_1") (pintype "passive"))
      (node (ref "M5") (pin "1") (pinfunction "EF_1") (pintype "passive"))
      (node (ref "M6") (pin "1") (pinfunction "EF_1") (pintype "passive"))
      (node (ref "P1") (pin "13") (pinfunction "GND_13") (pintype "passive"))
      (node (ref "P1") (pin "18") (pinfunction "GND_18") (pintype "passive"))
      (node (ref "P1") (pin "27") (pinfunction "GND_27") (pintype "passive"))
      (node (ref "P1") (pin "38") (pinfunction "GND_38") (pintype "passive"))
      (node (ref "P1") (pin "41") (pinfunction "GND_41") (pintype "passive"))
      (node (ref "P1") (pin "53") (pinfunction "GND_53") (pintype "passive"))
      (node (ref "P1") (pin "54") (pinfunction "GND_54") (pintype "passive"))
      (node (ref "P1") (pin "76") (pinfunction "GND_76") (pintype "passive"))
      (node (ref "P1") (pin "79") (pinfunction "GND_79") (pintype "passive"))
      (node (ref "P10") (pin "4") (pinfunction "4_4") (pintype "passive"))
      (node (ref "P10") (pin "7") (pinfunction "7_7") (pintype "passive"))
      (node (ref "P19") (pin "10") (pinfunction "MH1_10") (pintype "passive"))
      (node (ref "P19") (pin "11") (pinfunction "MH2_11") (pintype "passive"))
      (node (ref "P19") (pin "5") (pinfunction "5_5") (pintype "passive"))
      (node (ref "P2") (pin "15") (pinfunction "GND_15") (pintype "passive"))
      (node (ref "P2") (pin "20") (pinfunction "GND_20") (pintype "passive"))
      (node (ref "P2") (pin "28") (pinfunction "GND_28") (pintype "passive"))
      (node (ref "P2") (pin "29") (pinfunction "GND_29") (pintype "passive"))
      (node (ref "P2") (pin "46") (pinfunction "GND_46") (pintype "passive"))
      (node (ref "P2") (pin "47") (pinfunction "GND_47") (pintype "passive"))
      (node (ref "P2") (pin "57") (pinfunction "GND_57") (pintype "passive"))
      (node (ref "P2") (pin "64") (pinfunction "GND_64") (pintype "passive"))
      (node (ref "P2") (pin "71") (pinfunction "GND_71") (pintype "passive"))
      (node (ref "P2") (pin "76") (pinfunction "GND_76") (pintype "passive"))
      (node (ref "P9") (pin "4") (pinfunction "4_4") (pintype "passive"))
      (node (ref "P9") (pin "7") (pinfunction "7_7") (pintype "passive"))
      (node (ref "R27") (pin "1") (pinfunction "1_1") (pintype "passive"))
      (node (ref "U4") (pin "15") (pinfunction "GND_15") (pintype "passive"))
    )
    (net (code "143") (name "Net-(K2-B1)") (class "Default")
      (node (ref "K2") (pin "8") (pinfunction "B1_8") (pintype "passive"))
      (node (ref "R27") (pin "2") (pinfunction "2_2") (pintype "passive"))
    )
    (net (code "144") (name "Net-(K2-B2)") (class "Default")
      (node (ref "K2") (pin "7") (pinfunction "B2_7") (pintype "passive"))
      (node (ref "R28") (pin "2") (pinfunction "2_2") (pintype "passive"))
    )
    (net (code "145") (name "Net-(K2-B3)") (class "Default")
      (node (ref "K2") (pin "6") (pinfunction "B3_6") (pintype "passive"))
      (node (ref "R30") (pin "2") (pinfunction "2_2") (pintype "passive"))
    )
    (net (code "146") (name "Net-(K2-B4)") (class "Default")
      (node (ref "K2") (pin "5") (pinfunction "B4_5") (pintype "passive"))
      (node (ref "R31") (pin "2") (pinfunction "2_2") (pintype "passive"))
    )
    (net (code "147") (name "Net-(LED2-A)") (class "Default")
      (node (ref "LED2") (pin "1") (pinfunction "A_1") (pintype "passive"))
      (node (ref "R26") (pin "2") (pinfunction "2_2") (pintype "passive"))
    )
    (net (code "148") (name "Net-(U4-C1+)") (class "Default")
      (node (ref "C23") (pin "1") (pinfunction "1_1") (pintype "passive"))
      (node (ref "U4") (pin "1") (pinfunction "C1+_1") (pintype "passive"))
    )
    (net (code "149") (name "Net-(U4-C1-)") (class "Default")
      (node (ref "C23") (pin "2") (pinfunction "2_2") (pintype "passive"))
      (node (ref "U4") (pin "3") (pinfunction "C1-_3") (pintype "passive"))
    )
    (net (code "150") (name "Net-(U4-C2+)") (class "Default")
      (node (ref "C27") (pin "2") (pinfunction "2_2") (pintype "passive"))
      (node (ref "U4") (pin "4") (pinfunction "C2+_4") (pintype "passive"))
    )
    (net (code "151") (name "Net-(U4-C2-)") (class "Default")
      (node (ref "C27") (pin "1") (pinfunction "1_1") (pintype "passive"))
      (node (ref "U4") (pin "5") (pinfunction "C2-_5") (pintype "passive"))
    )
    (net (code "152") (name "Net-(U4-V+)") (class "Default")
      (node (ref "C25") (pin "2") (pinfunction "2_2") (pintype "passive"))
      (node (ref "U4") (pin "2") (pinfunction "V+_2") (pintype "passive"))
    )
    (net (code "153") (name "Net-(U4-V-)") (class "Default")
      (node (ref "C26") (pin "2") (pinfunction "2_2") (pintype "passive"))
      (node (ref "U4") (pin "6") (pinfunction "V-_6") (pintype "passive"))
    )
    (net (code "154") (name "VCC3V3") (class "Default")
      (node (ref "C24") (pin "2") (pinfunction "2_2") (pintype "passive"))
      (node (ref "R23") (pin "2") (pinfunction "2_2") (pintype "passive"))
      (node (ref "R26") (pin "1") (pinfunction "1_1") (pintype "passive"))
      (node (ref "R28") (pin "1") (pinfunction "1_1") (pintype "passive"))
      (node (ref "R29") (pin "2") (pinfunction "2_2") (pintype "passive"))
      (node (ref "R30") (pin "1") (pinfunction "1_1") (pintype "passive"))
      (node (ref "R31") (pin "1") (pinfunction "1_1") (pintype "passive"))
      (node (ref "R9") (pin "2") (pinfunction "2_2") (pintype "passive"))
      (node (ref "U4") (pin "16") (pinfunction "VCC_16") (pintype "passive"))
    )
    (net (code "155") (name "VCC5V") (class "Default")
      (node (ref "P10") (pin "5") (pinfunction "5_5") (pintype "passive"))
      (node (ref "P10") (pin "6") (pinfunction "6_6") (pintype "passive"))
      (node (ref "P9") (pin "5") (pinfunction "5_5") (pintype "passive"))
      (node (ref "P9") (pin "6") (pinfunction "6_6") (pintype "passive"))
      (node (ref "R10") (pin "2") (pinfunction "2_2") (pintype "passive"))
    )
    (net (code "156") (name "V_CORE5V") (class "Default")
      (node (ref "P1") (pin "78") (pinfunction "5V_SYS_78") (pintype "passive"))
      (node (ref "P1") (pin "80") (pinfunction "5V_SYS_80") (pintype "passive"))
    )
    (net (code "157") (name "unconnected-(P9-Pad1)") (class "Default")
      (node (ref "P9") (pin "1") (pinfunction "1_1") (pintype "passive+no_connect"))
    )
    (net (code "158") (name "unconnected-(P9-Pad2)") (class "Default")
      (node (ref "P9") (pin "2") (pinfunction "2_2") (pintype "passive+no_connect"))
    )
    (net (code "159") (name "unconnected-(P9-Pad9)") (class "Default")
      (node (ref "P9") (pin "9") (pinfunction "9_9") (pintype "passive+no_connect"))
    )
    (net (code "160") (name "unconnected-(P9-Pad10)") (class "Default")
      (node (ref "P9") (pin "10") (pinfunction "10_10") (pintype "passive+no_connect"))
    )
    (net (code "161") (name "unconnected-(P10-Pad2)") (class "Default")
      (node (ref "P10") (pin "2") (pinfunction "2_2") (pintype "passive+no_connect"))
    )
    (net (code "162") (name "unconnected-(P10-Pad9)") (class "Default")
      (node (ref "P10") (pin "9") (pinfunction "9_9") (pintype "passive+no_connect"))
    )
    (net (code "163") (name "unconnected-(P19-Pad1)") (class "Default")
      (node (ref "P19") (pin "1") (pinfunction "1_1") (pintype "passive+no_connect"))
    )
    (net (code "164") (name "unconnected-(P19-Pad4)") (class "Default")
      (node (ref "P19") (pin "4") (pinfunction "4_4") (pintype "passive+no_connect"))
    )
    (net (code "165") (name "unconnected-(P19-Pad6)") (class "Default")
      (node (ref "P19") (pin "6") (pinfunction "6_6") (pintype "passive+no_connect"))
    )
    (net (code "166") (name "unconnected-(P19-Pad7)") (class "Default")
      (node (ref "P19") (pin "7") (pinfunction "7_7") (pintype "passive+no_connect"))
    )
    (net (code "167") (name "unconnected-(P19-Pad8)") (class "Default")
      (node (ref "P19") (pin "8") (pinfunction "8_8") (pintype "passive+no_connect"))
    )
    (net (code "168") (name "unconnected-(P19-Pad9)") (class "Default")
      (node (ref "P19") (pin "9") (pinfunction "9_9") (pintype "passive+no_connect"))
    )
    (net (code "169") (name "unconnected-(U4-R1IN-Pad13)") (class "Default")
      (node (ref "U4") (pin "13") (pinfunction "R1IN_13") (pintype "passive+no_connect"))
    )
    (net (code "170") (name "unconnected-(U4-R1OUT-Pad12)") (class "Default")
      (node (ref "U4") (pin "12") (pinfunction "R1OUT_12") (pintype "passive+no_connect"))
    )
    (net (code "171") (name "unconnected-(U4-T1IN-Pad11)") (class "Default")
      (node (ref "U4") (pin "11") (pinfunction "T1IN_11") (pintype "passive+no_connect"))
    )
    (net (code "172") (name "unconnected-(U4-T1OUT-Pad14)") (class "Default")
      (node (ref "U4") (pin "14") (pinfunction "T1OUT_14") (pintype "passive+no_connect"))
    )
  )
)
